# Arduino_Nano_RGB_Led_Controller.net
KiCad netlist of a schematic drawn in EAGLE
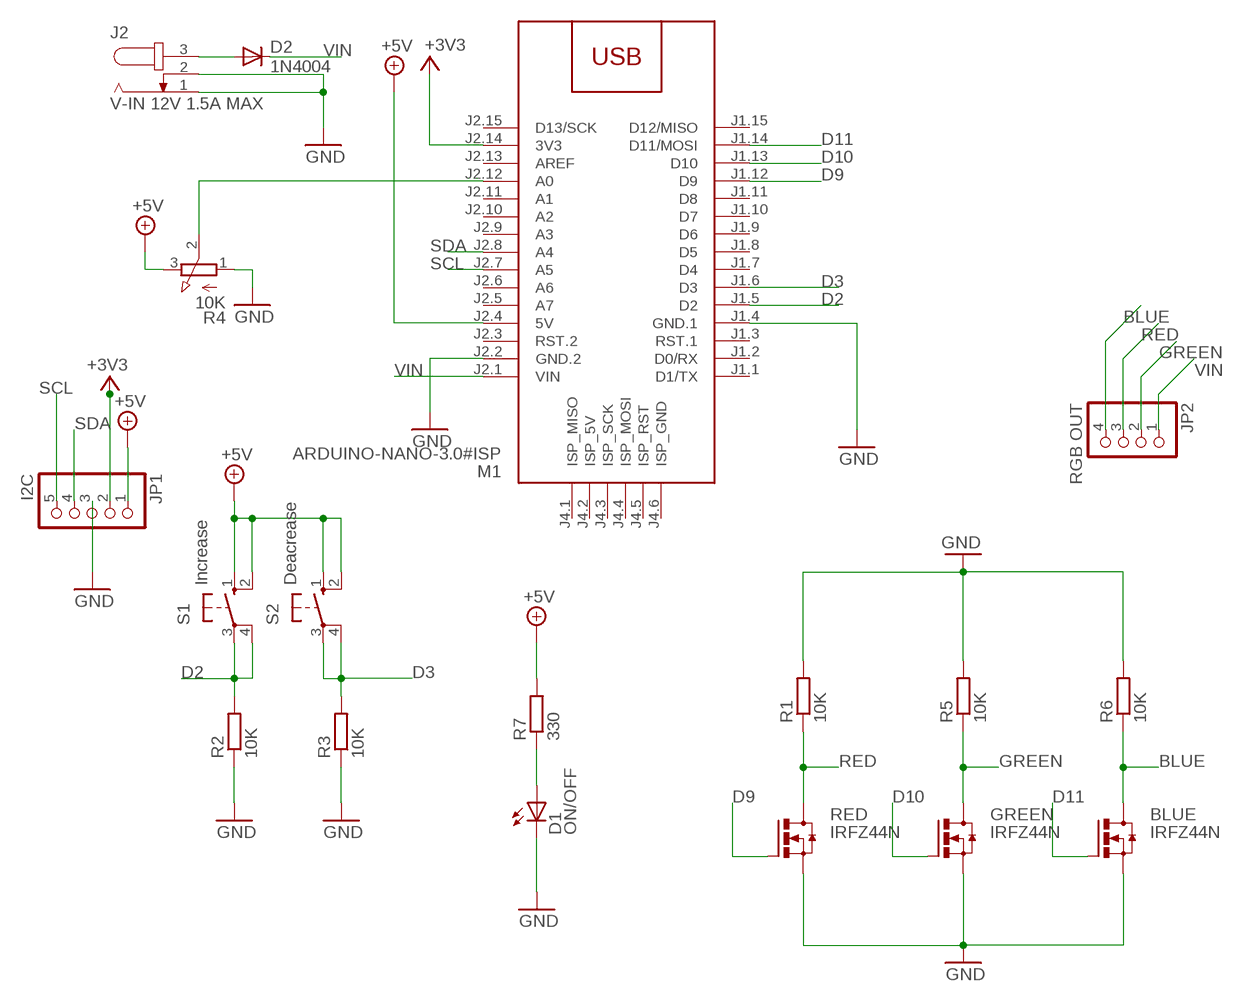
[diagram p0: schematic, sheet 1]

(export (version "E")
  (design (tool "Eeschema 10.0.6"))
  (components
    (comp (ref "BLUE")
      (value "IRFZ44N")
      (footprint "eagle-import:TO220V")
      (libsource (lib "eagle-import") (part "IRFZ44N"))
    )
    (comp (ref "D1")
      (value "ON/OFF")
      (footprint "eagle-import:CHIPLED_1206")
      (libsource (lib "eagle-import") (part "LEDCHIPLED_1206"))
    )
    (comp (ref "D2")
      (value "1N4004")
      (footprint "eagle-import:DO41-10")
      (libsource (lib "eagle-import") (part "1N4004"))
    )
    (comp (ref "GREEN")
      (value "IRFZ44N")
      (footprint "eagle-import:TO220V")
      (libsource (lib "eagle-import") (part "IRFZ44N"))
    )
    (comp (ref "J2")
      (value "V-IN 12V 1.5A MAX")
      (footprint "eagle-import:SPC4078")
      (libsource (lib "eagle-import") (part "JACK-PLUG1"))
    )
    (comp (ref "JP1")
      (value "I2C")
      (footprint "eagle-import:1_05X2MM")
      (libsource (lib "eagle-import") (part "PINHD-1X55X2MM"))
    )
    (comp (ref "JP2")
      (value "RGB OUT")
      (footprint "eagle-import:1X04")
      (libsource (lib "eagle-import") (part "PINHD-1X4"))
    )
    (comp (ref "M1")
      (value "ARDUINO-NANO-3.0#ISP")
      (footprint "eagle-import:ARDUINO-NANO-3.0#ISP")
      (libsource (lib "eagle-import") (part "ARDUINO-NANO-3.0#ISP"))
    )
    (comp (ref "R1")
      (value "10K")
      (footprint "eagle-import:M1206")
      (libsource (lib "eagle-import") (part "R-EU_M1206"))
    )
    (comp (ref "R2")
      (value "10K")
      (footprint "eagle-import:M1206")
      (libsource (lib "eagle-import") (part "R-EU_M1206"))
    )
    (comp (ref "R3")
      (value "10K")
      (footprint "eagle-import:M1206")
      (libsource (lib "eagle-import") (part "R-EU_M1206"))
    )
    (comp (ref "R4")
      (value "10K")
      (footprint "eagle-import:3RP_1610N")
      (libsource (lib "eagle-import") (part "3RP/1610N"))
    )
    (comp (ref "R5")
      (value "10K")
      (footprint "eagle-import:M1206")
      (libsource (lib "eagle-import") (part "R-EU_M1206"))
    )
    (comp (ref "R6")
      (value "10K")
      (footprint "eagle-import:M1206")
      (libsource (lib "eagle-import") (part "R-EU_M1206"))
    )
    (comp (ref "R7")
      (value "330")
      (footprint "eagle-import:M1206")
      (libsource (lib "eagle-import") (part "R-EU_M1206"))
    )
    (comp (ref "RED")
      (value "IRFZ44N")
      (footprint "eagle-import:TO220V")
      (libsource (lib "eagle-import") (part "IRFZ44N"))
    )
    (comp (ref "S1")
      (value "Increase")
      (footprint "eagle-import:B3F-10XX")
      (fields (field (name "MPN") "B3F-1000"))
      (libsource (lib "eagle-import") (part "10-XX"))
    )
    (comp (ref "S2")
      (value "Deacrease")
      (footprint "eagle-import:B3F-10XX")
      (fields (field (name "MPN") "B3F-1000"))
      (libsource (lib "eagle-import") (part "10-XX"))
    )
  )
  (nets
    (net (code "1") (name "+3V3") (class "Default")
      (node (ref "JP1") (pin "2") (pinfunction "2_2") (pintype "passive"))
      (node (ref "M1") (pin "J2.14") (pinfunction "3V3_J2.14") (pintype "power_in"))
    )
    (net (code "2") (name "+5V") (class "Default")
      (node (ref "JP1") (pin "1") (pinfunction "1_1") (pintype "passive"))
      (node (ref "M1") (pin "J2.4") (pinfunction "5V_J2.4") (pintype "power_in"))
      (node (ref "R4") (pin "3") (pinfunction "E_3") (pintype "passive"))
      (node (ref "R7") (pin "2") (pinfunction "2_2") (pintype "passive"))
      (node (ref "S1") (pin "1") (pinfunction "S_1") (pintype "passive"))
      (node (ref "S1") (pin "2") (pinfunction "S1_2") (pintype "passive"))
      (node (ref "S2") (pin "1") (pinfunction "S_1") (pintype "passive"))
      (node (ref "S2") (pin "2") (pinfunction "S1_2") (pintype "passive"))
    )
    (net (code "3") (name "/BLUE") (class "Default")
      (node (ref "BLUE") (pin "2") (pinfunction "D_2") (pintype "passive"))
      (node (ref "JP2") (pin "4") (pinfunction "4_4") (pintype "passive"))
      (node (ref "R6") (pin "1") (pinfunction "1_1") (pintype "passive"))
    )
    (net (code "4") (name "/D2") (class "Default")
      (node (ref "M1") (pin "J1.5") (pinfunction "D2_J1.5") (pintype "bidirectional"))
      (node (ref "R2") (pin "2") (pinfunction "2_2") (pintype "passive"))
      (node (ref "S1") (pin "3") (pinfunction "P_3") (pintype "passive"))
      (node (ref "S1") (pin "4") (pinfunction "P1_4") (pintype "passive"))
    )
    (net (code "5") (name "/D3") (class "Default")
      (node (ref "M1") (pin "J1.6") (pinfunction "D3_J1.6") (pintype "bidirectional"))
      (node (ref "R3") (pin "2") (pinfunction "2_2") (pintype "passive"))
      (node (ref "S2") (pin "3") (pinfunction "P_3") (pintype "passive"))
      (node (ref "S2") (pin "4") (pinfunction "P1_4") (pintype "passive"))
    )
    (net (code "6") (name "/D9") (class "Default")
      (node (ref "M1") (pin "J1.12") (pinfunction "D9_J1.12") (pintype "bidirectional"))
      (node (ref "RED") (pin "1") (pinfunction "G_1") (pintype "passive"))
    )
    (net (code "7") (name "/D10") (class "Default")
      (node (ref "GREEN") (pin "1") (pinfunction "G_1") (pintype "passive"))
      (node (ref "M1") (pin "J1.13") (pinfunction "D10_J1.13") (pintype "bidirectional"))
    )
    (net (code "8") (name "/D11") (class "Default")
      (node (ref "BLUE") (pin "1") (pinfunction "G_1") (pintype "passive"))
      (node (ref "M1") (pin "J1.14") (pinfunction "D11/MOSI_J1.14") (pintype "bidirectional"))
    )
    (net (code "9") (name "/GREEN") (class "Default")
      (node (ref "GREEN") (pin "2") (pinfunction "D_2") (pintype "passive"))
      (node (ref "JP2") (pin "2") (pinfunction "2_2") (pintype "passive"))
      (node (ref "R5") (pin "1") (pinfunction "1_1") (pintype "passive"))
    )
    (net (code "10") (name "/RED") (class "Default")
      (node (ref "JP2") (pin "3") (pinfunction "3_3") (pintype "passive"))
      (node (ref "R1") (pin "1") (pinfunction "1_1") (pintype "passive"))
      (node (ref "RED") (pin "2") (pinfunction "D_2") (pintype "passive"))
    )
    (net (code "11") (name "/SCL") (class "Default")
      (node (ref "JP1") (pin "5") (pinfunction "5_5") (pintype "passive"))
      (node (ref "M1") (pin "J2.7") (pinfunction "A5_J2.7") (pintype "bidirectional"))
    )
    (net (code "12") (name "/SDA") (class "Default")
      (node (ref "JP1") (pin "4") (pinfunction "4_4") (pintype "passive"))
      (node (ref "M1") (pin "J2.8") (pinfunction "A4_J2.8") (pintype "bidirectional"))
    )
    (net (code "13") (name "/VIN") (class "Default")
      (node (ref "D2") (pin "C") (pinfunction "C_C") (pintype "passive"))
      (node (ref "JP2") (pin "1") (pinfunction "1_1") (pintype "passive"))
      (node (ref "M1") (pin "J2.1") (pinfunction "VIN_J2.1") (pintype "power_in"))
    )
    (net (code "14") (name "GND") (class "Default")
      (node (ref "BLUE") (pin "3") (pinfunction "S_3") (pintype "passive"))
      (node (ref "D1") (pin "C") (pinfunction "C_C") (pintype "passive"))
      (node (ref "GREEN") (pin "3") (pinfunction "S_3") (pintype "passive"))
      (node (ref "J2") (pin "1") (pinfunction "1_1") (pintype "passive"))
      (node (ref "J2") (pin "2") (pinfunction "2_2") (pintype "passive"))
      (node (ref "JP1") (pin "3") (pinfunction "3_3") (pintype "passive"))
      (node (ref "M1") (pin "J1.4") (pinfunction "GND.1_J1.4") (pintype "power_in"))
      (node (ref "M1") (pin "J2.2") (pinfunction "GND.2_J2.2") (pintype "power_in"))
      (node (ref "R1") (pin "2") (pinfunction "2_2") (pintype "passive"))
      (node (ref "R2") (pin "1") (pinfunction "1_1") (pintype "passive"))
      (node (ref "R3") (pin "1") (pinfunction "1_1") (pintype "passive"))
      (node (ref "R4") (pin "1") (pinfunction "A_1") (pintype "passive"))
      (node (ref "R5") (pin "2") (pinfunction "2_2") (pintype "passive"))
      (node (ref "R6") (pin "2") (pinfunction "2_2") (pintype "passive"))
      (node (ref "RED") (pin "3") (pinfunction "S_3") (pintype "passive"))
    )
    (net (code "15") (name "Net-(D1-PadA)") (class "Default")
      (node (ref "D1") (pin "A") (pinfunction "A_A") (pintype "passive"))
      (node (ref "R7") (pin "1") (pinfunction "1_1") (pintype "passive"))
    )
    (net (code "16") (name "Net-(D2-PadA)") (class "Default")
      (node (ref "D2") (pin "A") (pinfunction "A_A") (pintype "passive"))
      (node (ref "J2") (pin "3") (pinfunction "3_3") (pintype "passive"))
    )
    (net (code "17") (name "Net-(M1-A0)") (class "Default")
      (node (ref "M1") (pin "J2.12") (pinfunction "A0_J2.12") (pintype "bidirectional"))
      (node (ref "R4") (pin "2") (pinfunction "S_2") (pintype "passive"))
    )
    (net (code "18") (name "unconnected-(M1-A1-PadJ2.11)") (class "Default")
      (node (ref "M1") (pin "J2.11") (pinfunction "A1_J2.11") (pintype "bidirectional"))
    )
    (net (code "19") (name "unconnected-(M1-A2-PadJ2.10)") (class "Default")
      (node (ref "M1") (pin "J2.10") (pinfunction "A2_J2.10") (pintype "bidirectional"))
    )
    (net (code "20") (name "unconnected-(M1-A3-PadJ2.9)") (class "Default")
      (node (ref "M1") (pin "J2.9") (pinfunction "A3_J2.9") (pintype "bidirectional"))
    )
    (net (code "21") (name "unconnected-(M1-A6-PadJ2.6)") (class "Default")
      (node (ref "M1") (pin "J2.6") (pinfunction "A6_J2.6") (pintype "bidirectional"))
    )
    (net (code "22") (name "unconnected-(M1-A7-PadJ2.5)") (class "Default")
      (node (ref "M1") (pin "J2.5") (pinfunction "A7_J2.5") (pintype "bidirectional"))
    )
    (net (code "23") (name "unconnected-(M1-AREF-PadJ2.13)") (class "Default")
      (node (ref "M1") (pin "J2.13") (pinfunction "AREF_J2.13") (pintype "bidirectional"))
    )
    (net (code "24") (name "unconnected-(M1-D0{slash}RX-PadJ1.2)") (class "Default")
      (node (ref "M1") (pin "J1.2") (pinfunction "D0/RX_J1.2") (pintype "bidirectional"))
    )
    (net (code "25") (name "unconnected-(M1-D1{slash}TX-PadJ1.1)") (class "Default")
      (node (ref "M1") (pin "J1.1") (pinfunction "D1/TX_J1.1") (pintype "bidirectional"))
    )
    (net (code "26") (name "unconnected-(M1-D4-PadJ1.7)") (class "Default")
      (node (ref "M1") (pin "J1.7") (pinfunction "D4_J1.7") (pintype "bidirectional"))
    )
    (net (code "27") (name "unconnected-(M1-D5-PadJ1.8)") (class "Default")
      (node (ref "M1") (pin "J1.8") (pinfunction "D5_J1.8") (pintype "bidirectional"))
    )
    (net (code "28") (name "unconnected-(M1-D6-PadJ1.9)") (class "Default")
      (node (ref "M1") (pin "J1.9") (pinfunction "D6_J1.9") (pintype "bidirectional"))
    )
    (net (code "29") (name "unconnected-(M1-D7-PadJ1.10)") (class "Default")
      (node (ref "M1") (pin "J1.10") (pinfunction "D7_J1.10") (pintype "bidirectional"))
    )
    (net (code "30") (name "unconnected-(M1-D8-PadJ1.11)") (class "Default")
      (node (ref "M1") (pin "J1.11") (pinfunction "D8_J1.11") (pintype "bidirectional"))
    )
    (net (code "31") (name "unconnected-(M1-D12{slash}MISO-PadJ1.15)") (class "Default")
      (node (ref "M1") (pin "J1.15") (pinfunction "D12/MISO_J1.15") (pintype "bidirectional"))
    )
    (net (code "32") (name "unconnected-(M1-D13{slash}SCK-PadJ2.15)") (class "Default")
      (node (ref "M1") (pin "J2.15") (pinfunction "D13/SCK_J2.15") (pintype "bidirectional"))
    )
    (net (code "33") (name "unconnected-(M1-ISP_5V-PadJ4.2)") (class "Default")
      (node (ref "M1") (pin "J4.2") (pinfunction "ISP_5V_J4.2") (pintype "bidirectional"))
    )
    (net (code "34") (name "unconnected-(M1-ISP_GND-PadJ4.6)") (class "Default")
      (node (ref "M1") (pin "J4.6") (pinfunction "ISP_GND_J4.6") (pintype "bidirectional"))
    )
    (net (code "35") (name "unconnected-(M1-ISP_MISO-PadJ4.1)") (class "Default")
      (node (ref "M1") (pin "J4.1") (pinfunction "ISP_MISO_J4.1") (pintype "bidirectional"))
    )
    (net (code "36") (name "unconnected-(M1-ISP_MOSI-PadJ4.4)") (class "Default")
      (node (ref "M1") (pin "J4.4") (pinfunction "ISP_MOSI_J4.4") (pintype "bidirectional"))
    )
    (net (code "37") (name "unconnected-(M1-ISP_RST-PadJ4.5)") (class "Default")
      (node (ref "M1") (pin "J4.5") (pinfunction "ISP_RST_J4.5") (pintype "bidirectional"))
    )
    (net (code "38") (name "unconnected-(M1-ISP_SCK-PadJ4.3)") (class "Default")
      (node (ref "M1") (pin "J4.3") (pinfunction "ISP_SCK_J4.3") (pintype "bidirectional"))
    )
    (net (code "39") (name "unconnected-(M1-RST.1-PadJ1.3)") (class "Default")
      (node (ref "M1") (pin "J1.3") (pinfunction "RST.1_J1.3") (pintype "bidirectional"))
    )
    (net (code "40") (name "unconnected-(M1-RST.2-PadJ2.3)") (class "Default")
      (node (ref "M1") (pin "J2.3") (pinfunction "RST.2_J2.3") (pintype "bidirectional"))
    )
  )
)
